# TX16S_ISRM_Adapter.net
KiCad netlist of a schematic drawn in EAGLE
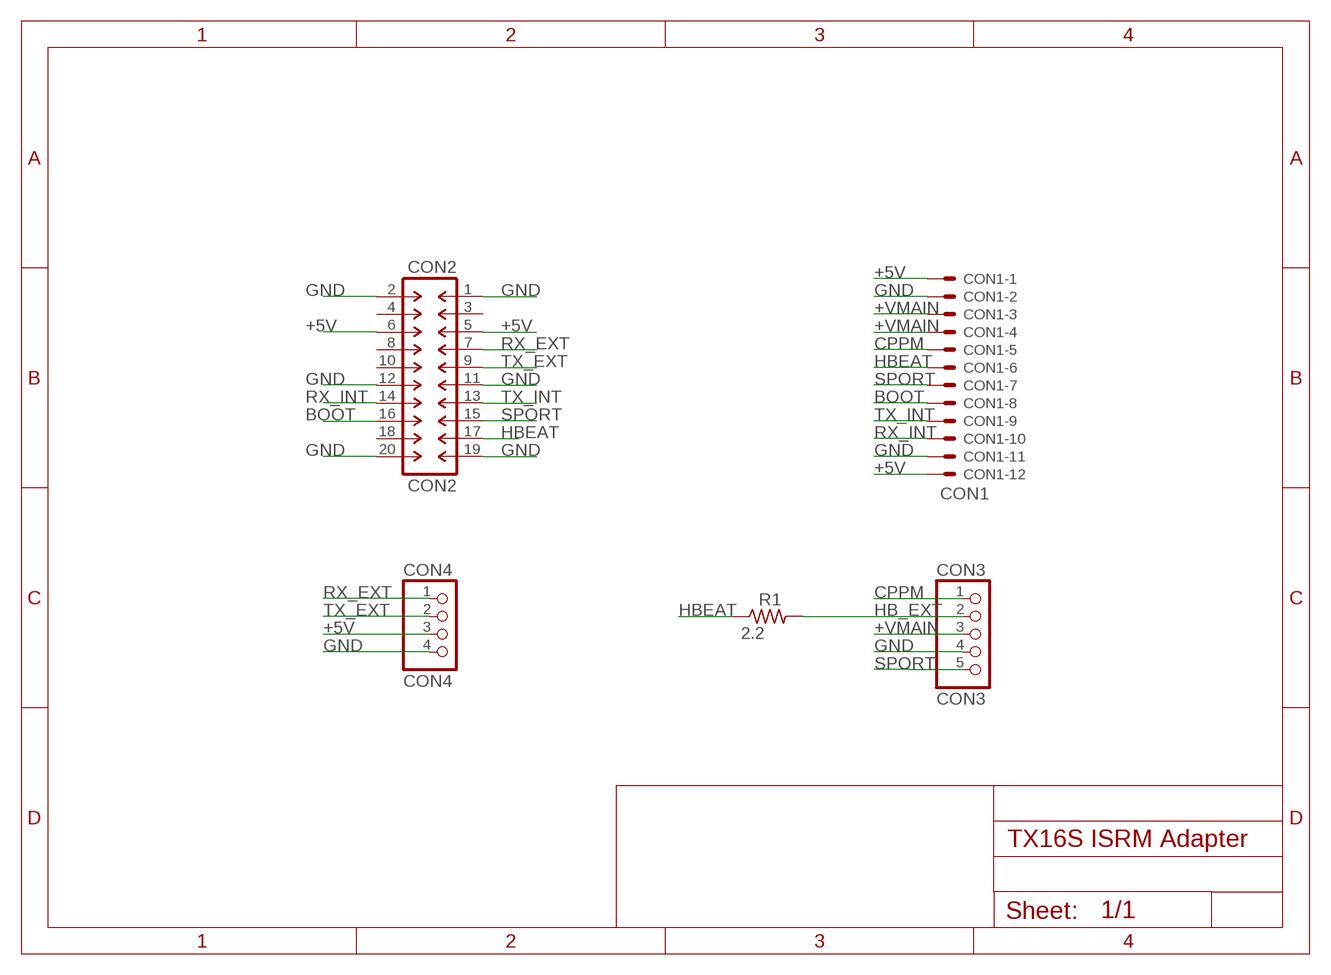
[diagram p0: schematic, sheet 1]

(export (version "E")
  (design (tool "Eeschema 10.0.6"))
  (components
    (comp (ref "CON1")
      (value "CON1")
      (footprint "eagle-import:53048-12")
      (libsource (lib "eagle-import") (part "53?-12048"))
    )
    (comp (ref "CON2")
      (value "CON2")
      (footprint "eagle-import:DIL-2MM-2X10_M")
      (libsource (lib "eagle-import") (part "M-2X10-DIL-2MM_M"))
    )
    (comp (ref "CON3")
      (value "CON3")
      (footprint "eagle-import:1X05")
      (libsource (lib "eagle-import") (part "PINHD-1X5"))
    )
    (comp (ref "CON4")
      (value "CON4")
      (footprint "eagle-import:1X04")
      (libsource (lib "eagle-import") (part "PINHD-1X4"))
    )
    (comp (ref "R1")
      (value "2.2")
      (footprint "eagle-import:R0603")
      (libsource (lib "eagle-import") (part "R-US_R0603"))
    )
  )
  (nets
    (net (code "1") (name "/+5V") (class "Default")
      (node (ref "CON1") (pin "1") (pinfunction "S_1") (pintype "passive"))
      (node (ref "CON1") (pin "12") (pinfunction "S_12") (pintype "passive"))
      (node (ref "CON2") (pin "5") (pinfunction "5_5") (pintype "passive"))
      (node (ref "CON2") (pin "6") (pinfunction "6_6") (pintype "passive"))
      (node (ref "CON4") (pin "3") (pinfunction "3_3") (pintype "passive"))
    )
    (net (code "2") (name "/+VMAIN") (class "Default")
      (node (ref "CON1") (pin "3") (pinfunction "S_3") (pintype "passive"))
      (node (ref "CON1") (pin "4") (pinfunction "S_4") (pintype "passive"))
      (node (ref "CON3") (pin "3") (pinfunction "3_3") (pintype "passive"))
    )
    (net (code "3") (name "/BOOT") (class "Default")
      (node (ref "CON1") (pin "8") (pinfunction "S_8") (pintype "passive"))
      (node (ref "CON2") (pin "16") (pinfunction "16_16") (pintype "passive"))
    )
    (net (code "4") (name "/CPPM") (class "Default")
      (node (ref "CON1") (pin "5") (pinfunction "S_5") (pintype "passive"))
      (node (ref "CON3") (pin "1") (pinfunction "1_1") (pintype "passive"))
    )
    (net (code "5") (name "/GND") (class "Default")
      (node (ref "CON1") (pin "11") (pinfunction "S_11") (pintype "passive"))
      (node (ref "CON1") (pin "2") (pinfunction "S_2") (pintype "passive"))
      (node (ref "CON2") (pin "1") (pinfunction "1_1") (pintype "passive"))
      (node (ref "CON2") (pin "11") (pinfunction "11_11") (pintype "passive"))
      (node (ref "CON2") (pin "12") (pinfunction "12_12") (pintype "passive"))
      (node (ref "CON2") (pin "19") (pinfunction "19_19") (pintype "passive"))
      (node (ref "CON2") (pin "2") (pinfunction "2_2") (pintype "passive"))
      (node (ref "CON2") (pin "20") (pinfunction "20_20") (pintype "passive"))
      (node (ref "CON3") (pin "4") (pinfunction "4_4") (pintype "passive"))
      (node (ref "CON4") (pin "4") (pinfunction "GND_4") (pintype "passive"))
    )
    (net (code "6") (name "/HBEAT") (class "Default")
      (node (ref "CON1") (pin "6") (pinfunction "S_6") (pintype "passive"))
      (node (ref "CON2") (pin "17") (pinfunction "17_17") (pintype "passive"))
      (node (ref "R1") (pin "1") (pinfunction "1_1") (pintype "passive"))
    )
    (net (code "7") (name "/HB_EXT") (class "Default")
      (node (ref "CON3") (pin "2") (pinfunction "2_2") (pintype "passive"))
      (node (ref "R1") (pin "2") (pinfunction "2_2") (pintype "passive"))
    )
    (net (code "8") (name "/RX_EXT") (class "Default")
      (node (ref "CON2") (pin "7") (pinfunction "7_7") (pintype "passive"))
      (node (ref "CON4") (pin "1") (pinfunction "1_1") (pintype "passive"))
    )
    (net (code "9") (name "/RX_INT") (class "Default")
      (node (ref "CON1") (pin "10") (pinfunction "S_10") (pintype "passive"))
      (node (ref "CON2") (pin "14") (pinfunction "14_14") (pintype "passive"))
    )
    (net (code "10") (name "/SPORT") (class "Default")
      (node (ref "CON1") (pin "7") (pinfunction "S_7") (pintype "passive"))
      (node (ref "CON2") (pin "15") (pinfunction "15_15") (pintype "passive"))
      (node (ref "CON3") (pin "5") (pinfunction "5_5") (pintype "passive"))
    )
    (net (code "11") (name "/TX_EXT") (class "Default")
      (node (ref "CON2") (pin "9") (pinfunction "9_9") (pintype "passive"))
      (node (ref "CON4") (pin "2") (pinfunction "2_2") (pintype "passive"))
    )
    (net (code "12") (name "/TX_INT") (class "Default")
      (node (ref "CON1") (pin "9") (pinfunction "S_9") (pintype "passive"))
      (node (ref "CON2") (pin "13") (pinfunction "13_13") (pintype "passive"))
    )
    (net (code "13") (name "unconnected-(CON2-Pad3)") (class "Default")
      (node (ref "CON2") (pin "3") (pinfunction "3_3") (pintype "passive"))
    )
    (net (code "14") (name "unconnected-(CON2-Pad4)") (class "Default")
      (node (ref "CON2") (pin "4") (pinfunction "4_4") (pintype "passive"))
    )
    (net (code "15") (name "unconnected-(CON2-Pad8)") (class "Default")
      (node (ref "CON2") (pin "8") (pinfunction "8_8") (pintype "passive"))
    )
    (net (code "16") (name "unconnected-(CON2-Pad10)") (class "Default")
      (node (ref "CON2") (pin "10") (pinfunction "10_10") (pintype "passive"))
    )
    (net (code "17") (name "unconnected-(CON2-Pad18)") (class "Default")
      (node (ref "CON2") (pin "18") (pinfunction "18_18") (pintype "passive"))
    )
  )
)
